# CPU.net
KiCad netlist of a schematic drawn in Altium Designer
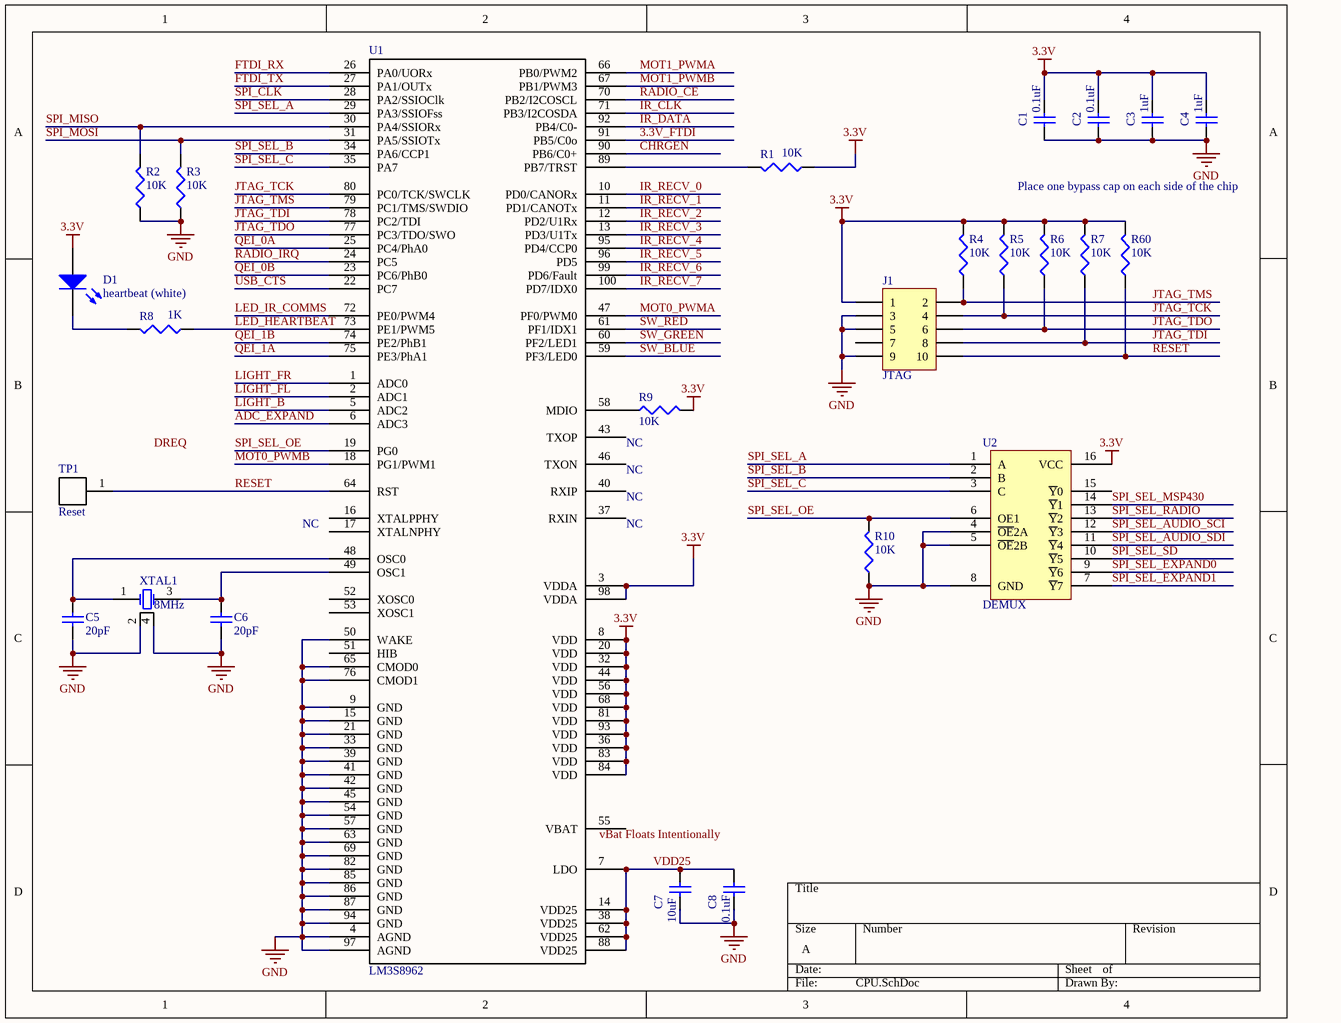
[diagram p0: CPU.SchDoc]

(export (version "E")
  (design (tool "Eeschema 10.0.6"))
  (components
    (comp (ref "C1")
      (value "0.1uF")
      (footprint "CAPC1005L")
      (description "Capacitor (Semiconductor SIM Model)")
      (fields (field (name "Comment") "Cap Semi") (field (name "PUBLISHER") "Altium Limited"))
      (libsource (lib "Miscellaneous Devices") (part "Cap Semi"))
    )
    (comp (ref "C2")
      (value "0.1uF")
      (footprint "CAPC1005L")
      (description "Capacitor (Semiconductor SIM Model)")
      (fields (field (name "Comment") "Cap Semi") (field (name "PUBLISHER") "Altium Limited"))
      (libsource (lib "Miscellaneous Devices") (part "Cap Semi"))
    )
    (comp (ref "C3")
      (value "1uF")
      (footprint "CAPC1608L")
      (description "Capacitor (Semiconductor SIM Model)")
      (fields (field (name "Comment") "Cap Semi") (field (name "PUBLISHER") "Altium Limited"))
      (libsource (lib "Miscellaneous Devices") (part "Cap Semi"))
    )
    (comp (ref "C4")
      (value "1uF")
      (footprint "CAPC1608L")
      (description "Capacitor (Semiconductor SIM Model)")
      (fields (field (name "Comment") "Cap Semi") (field (name "PUBLISHER") "Altium Limited"))
      (libsource (lib "Miscellaneous Devices") (part "Cap Semi"))
    )
    (comp (ref "C5")
      (value "20pF")
      (footprint "CAPC1005L")
      (description "Capacitor (Semiconductor SIM Model)")
      (fields (field (name "Comment") "Cap Semi") (field (name "PUBLISHER") "Altium Limited"))
      (libsource (lib "Miscellaneous Devices") (part "Cap Semi"))
    )
    (comp (ref "C6")
      (value "20pF")
      (footprint "CAPC1005L")
      (description "Capacitor (Semiconductor SIM Model)")
      (fields (field (name "Comment") "Cap Semi") (field (name "PUBLISHER") "Altium Limited"))
      (libsource (lib "Miscellaneous Devices") (part "Cap Semi"))
    )
    (comp (ref "C7")
      (value "10uF")
      (footprint "CAPC1608L")
      (description "Capacitor (Semiconductor SIM Model)")
      (fields (field (name "Comment") "Cap Semi") (field (name "PUBLISHER") "Altium Limited"))
      (libsource (lib "Miscellaneous Devices") (part "Cap Semi"))
    )
    (comp (ref "C8")
      (value "0.1uF")
      (footprint "CAPC1005L")
      (description "Capacitor (Semiconductor SIM Model)")
      (fields (field (name "Comment") "Cap Semi") (field (name "PUBLISHER") "Altium Limited"))
      (libsource (lib "Miscellaneous Devices") (part "Cap Semi"))
    )
    (comp (ref "D1")
      (value "heartbeat (white)")
      (footprint "SurfaceMount(603)")
      (libsource (lib "mrone") (part "LED"))
    )
    (comp (ref "J1")
      (value "JTAG")
      (footprint "JTAG-10")
      (description "Header, 5-Pin, Dual row, Right Angle")
      (fields (field (name "PUBLISHER") "Altium Limited"))
      (libsource (lib "Miscellaneous Connectors") (part "Header 5X2H"))
    )
    (comp (ref "R1")
      (value "10K")
      (footprint "RESC1608L")
      (description "Resistor")
      (fields (field (name "Comment") "Res3") (field (name "PUBLISHER") "Altium Limited"))
      (libsource (lib "Miscellaneous Devices") (part "Res3"))
    )
    (comp (ref "R2")
      (value "10K")
      (footprint "RESC1608L")
      (description "Resistor")
      (fields (field (name "Comment") "Res3") (field (name "PUBLISHER") "Altium Limited"))
      (libsource (lib "Miscellaneous Devices") (part "Res3"))
    )
    (comp (ref "R3")
      (value "10K")
      (footprint "RESC1608L")
      (description "Resistor")
      (fields (field (name "Comment") "Res3") (field (name "PUBLISHER") "Altium Limited"))
      (libsource (lib "Miscellaneous Devices") (part "Res3"))
    )
    (comp (ref "R4")
      (value "10K")
      (footprint "RESC1608L")
      (description "Resistor")
      (fields (field (name "Comment") "Res3") (field (name "PUBLISHER") "Altium Limited"))
      (libsource (lib "Miscellaneous Devices") (part "Res3"))
    )
    (comp (ref "R5")
      (value "10K")
      (footprint "RESC1608L")
      (description "Resistor")
      (fields (field (name "Comment") "Res3") (field (name "PUBLISHER") "Altium Limited"))
      (libsource (lib "Miscellaneous Devices") (part "Res3"))
    )
    (comp (ref "R6")
      (value "10K")
      (footprint "RESC1608L")
      (description "Resistor")
      (fields (field (name "Comment") "Res3") (field (name "PUBLISHER") "Altium Limited"))
      (libsource (lib "Miscellaneous Devices") (part "Res3"))
    )
    (comp (ref "R7")
      (value "10K")
      (footprint "RESC1608L")
      (description "Resistor")
      (fields (field (name "Comment") "Res3") (field (name "PUBLISHER") "Altium Limited"))
      (libsource (lib "Miscellaneous Devices") (part "Res3"))
    )
    (comp (ref "R8")
      (value "1K")
      (footprint "RESC1608L")
      (description "Resistor")
      (fields (field (name "Comment") "Res3") (field (name "PUBLISHER") "Altium Limited"))
      (libsource (lib "Miscellaneous Devices") (part "Res3"))
    )
    (comp (ref "R9")
      (value "10K")
      (footprint "RESC1608L")
      (description "Resistor")
      (fields (field (name "Comment") "Res3") (field (name "PUBLISHER") "Altium Limited"))
      (libsource (lib "Miscellaneous Devices") (part "Res3"))
    )
    (comp (ref "R10")
      (value "10K")
      (footprint "RESC1608L")
      (description "Resistor")
      (fields (field (name "Comment") "Res3") (field (name "PUBLISHER") "Altium Limited"))
      (libsource (lib "Miscellaneous Devices") (part "Res3"))
    )
    (comp (ref "R60")
      (value "10K")
      (footprint "RESC1608L")
      (description "Resistor")
      (fields (field (name "Comment") "Res3") (field (name "PUBLISHER") "Altium Limited"))
      (libsource (lib "Miscellaneous Devices") (part "Res3"))
    )
    (comp (ref "TP1") (value "Reset") (footprint "TestPoint") (libsource (lib "mrone") (part "TestPoint")))
    (comp (ref "U1")
      (value "LM3S8962")
      (footprint "LQFP-100")
      (libsource (lib "Schematic Components") (part "LM3S8962"))
    )
    (comp (ref "U2") (value "DEMUX") (footprint "TSSOP-16") (libsource (lib "mrone") (part "DEMUX")))
    (comp (ref "XTAL1") (value "8MHz") (footprint "CRYSTAL") (libsource (lib "mrone") (part "Crystal")))
  )
  (nets
    (net (code "1") (name "/3.3V_FTDI") (class "Default")
      (node (ref "U1") (pin "91") (pinfunction "PB5/C0o_91") (pintype "passive"))
    )
    (net (code "2") (name "/ADC_EXPAND") (class "Default")
      (node (ref "U1") (pin "6") (pinfunction "ADC3_6") (pintype "passive"))
    )
    (net (code "3") (name "/CHRGEN") (class "Default")
      (node (ref "U1") (pin "90") (pinfunction "PB6/C0+_90") (pintype "passive"))
    )
    (net (code "5") (name "/FTDI_RX") (class "Default")
      (node (ref "U1") (pin "26") (pinfunction "PA0/UORx_26") (pintype "passive"))
    )
    (net (code "6") (name "/FTDI_TX") (class "Default")
      (node (ref "U1") (pin "27") (pinfunction "PA1/OUTx_27") (pintype "passive"))
    )
    (net (code "7") (name "/IR_CLK") (class "Default")
      (node (ref "U1") (pin "71") (pinfunction "PB3/I2COSDA_71") (pintype "passive"))
    )
    (net (code "8") (name "/IR_DATA") (class "Default")
      (node (ref "U1") (pin "92") (pinfunction "PB4/C0-_92") (pintype "passive"))
    )
    (net (code "9") (name "/IR_RECV_0") (class "Default")
      (node (ref "U1") (pin "10") (pinfunction "PD0/CANORx_10") (pintype "passive"))
    )
    (net (code "10") (name "/IR_RECV_1") (class "Default")
      (node (ref "U1") (pin "11") (pinfunction "PD1/CANOTx_11") (pintype "passive"))
    )
    (net (code "11") (name "/IR_RECV_2") (class "Default")
      (node (ref "U1") (pin "12") (pinfunction "PD2/U1Rx_12") (pintype "passive"))
    )
    (net (code "12") (name "/IR_RECV_3") (class "Default")
      (node (ref "U1") (pin "13") (pinfunction "PD3/U1Tx_13") (pintype "passive"))
    )
    (net (code "13") (name "/IR_RECV_4") (class "Default")
      (node (ref "U1") (pin "95") (pinfunction "PD4/CCP0_95") (pintype "passive"))
    )
    (net (code "14") (name "/IR_RECV_5") (class "Default")
      (node (ref "U1") (pin "96") (pinfunction "PD5_96") (pintype "passive"))
    )
    (net (code "15") (name "/IR_RECV_6") (class "Default")
      (node (ref "U1") (pin "99") (pinfunction "PD6/Fault_99") (pintype "passive"))
    )
    (net (code "16") (name "/IR_RECV_7") (class "Default")
      (node (ref "U1") (pin "100") (pinfunction "PD7/IDX0_100") (pintype "passive"))
    )
    (net (code "17") (name "/JTAG_TCK") (class "Default")
      (node (ref "J1") (pin "4") (pinfunction "4_4") (pintype "passive"))
      (node (ref "R5") (pin "1") (pinfunction "1_1") (pintype "passive"))
      (node (ref "U1") (pin "80") (pinfunction "PC0/TCK/SWCLK_80") (pintype "passive"))
    )
    (net (code "18") (name "/JTAG_TDI") (class "Default")
      (node (ref "J1") (pin "8") (pinfunction "8_8") (pintype "passive"))
      (node (ref "R7") (pin "1") (pinfunction "1_1") (pintype "passive"))
      (node (ref "U1") (pin "78") (pinfunction "PC2/TDI_78") (pintype "passive"))
    )
    (net (code "19") (name "/JTAG_TDO") (class "Default")
      (node (ref "J1") (pin "6") (pinfunction "6_6") (pintype "passive"))
      (node (ref "R6") (pin "1") (pinfunction "1_1") (pintype "passive"))
      (node (ref "U1") (pin "77") (pinfunction "PC3/TDO/SWO_77") (pintype "passive"))
    )
    (net (code "20") (name "/JTAG_TMS") (class "Default")
      (node (ref "J1") (pin "2") (pinfunction "2_2") (pintype "passive"))
      (node (ref "R4") (pin "1") (pinfunction "1_1") (pintype "passive"))
      (node (ref "U1") (pin "79") (pinfunction "PC1/TMS/SWDIO_79") (pintype "passive"))
    )
    (net (code "21") (name "/LED_HEARTBEAT") (class "Default")
      (node (ref "R8") (pin "1") (pinfunction "1_1") (pintype "passive"))
      (node (ref "U1") (pin "73") (pinfunction "PE1/PWM5_73") (pintype "passive"))
    )
    (net (code "22") (name "/LED_IR_COMMS") (class "Default")
      (node (ref "U1") (pin "72") (pinfunction "PE0/PWM4_72") (pintype "passive"))
    )
    (net (code "23") (name "/LIGHT_B") (class "Default")
      (node (ref "U1") (pin "5") (pinfunction "ADC2_5") (pintype "passive"))
    )
    (net (code "24") (name "/LIGHT_FL") (class "Default")
      (node (ref "U1") (pin "2") (pinfunction "ADC1_2") (pintype "passive"))
    )
    (net (code "25") (name "/LIGHT_FR") (class "Default")
      (node (ref "U1") (pin "1") (pinfunction "ADC0_1") (pintype "passive"))
    )
    (net (code "26") (name "/MOT0_PWMA") (class "Default")
      (node (ref "U1") (pin "47") (pinfunction "PF0/PWM0_47") (pintype "passive"))
    )
    (net (code "27") (name "/MOT0_PWMB") (class "Default")
      (node (ref "U1") (pin "18") (pinfunction "PG1/PWM1_18") (pintype "passive"))
    )
    (net (code "28") (name "/MOT1_PWMA") (class "Default")
      (node (ref "U1") (pin "66") (pinfunction "PB0/PWM2_66") (pintype "passive"))
    )
    (net (code "29") (name "/MOT1_PWMB") (class "Default")
      (node (ref "U1") (pin "67") (pinfunction "PB1/PWM3_67") (pintype "passive"))
    )
    (net (code "30") (name "/QEI_0A") (class "Default")
      (node (ref "U1") (pin "25") (pinfunction "PC4/PhA0_25") (pintype "passive"))
    )
    (net (code "31") (name "/QEI_0B") (class "Default")
      (node (ref "U1") (pin "23") (pinfunction "PC6/PhB0_23") (pintype "passive"))
    )
    (net (code "32") (name "/QEI_1A") (class "Default")
      (node (ref "U1") (pin "75") (pinfunction "PE3/PhA1_75") (pintype "passive"))
    )
    (net (code "33") (name "/QEI_1B") (class "Default")
      (node (ref "U1") (pin "74") (pinfunction "PE2/PhB1_74") (pintype "passive"))
    )
    (net (code "34") (name "/RADIO_CE") (class "Default")
      (node (ref "U1") (pin "70") (pinfunction "PB2/I2COSCL_70") (pintype "passive"))
    )
    (net (code "35") (name "/RADIO_IRQ") (class "Default")
      (node (ref "U1") (pin "24") (pinfunction "PC5_24") (pintype "passive"))
    )
    (net (code "36") (name "/RESET") (class "Default")
      (node (ref "J1") (pin "10") (pinfunction "10_10") (pintype "passive"))
      (node (ref "R60") (pin "1") (pinfunction "1_1") (pintype "passive"))
      (node (ref "TP1") (pin "1") (pintype "passive"))
      (node (ref "U1") (pin "64") (pinfunction "RST_64") (pintype "passive"))
    )
    (net (code "37") (name "/SPI_CLK") (class "Default")
      (node (ref "U1") (pin "28") (pinfunction "PA2/SSIOClk_28") (pintype "passive"))
    )
    (net (code "38") (name "/SPI_MISO") (class "Default")
      (node (ref "R2") (pin "2") (pinfunction "2_2") (pintype "passive"))
      (node (ref "U1") (pin "30") (pinfunction "PA4/SSIORx_30") (pintype "passive"))
    )
    (net (code "39") (name "/SPI_MOSI") (class "Default")
      (node (ref "R3") (pin "2") (pinfunction "2_2") (pintype "passive"))
      (node (ref "U1") (pin "31") (pinfunction "PA5/SSIOTx_31") (pintype "passive"))
    )
    (net (code "40") (name "/SPI_SEL_A") (class "Default")
      (node (ref "U1") (pin "29") (pinfunction "PA3/SSIOFss_29") (pintype "passive"))
      (node (ref "U2") (pin "1") (pinfunction "A_1") (pintype "passive"))
    )
    (net (code "41") (name "/SPI_SEL_AUDIO_SCI") (class "Default")
      (node (ref "U2") (pin "12") (pinfunction "~{Y}3_12") (pintype "passive"))
    )
    (net (code "42") (name "/SPI_SEL_AUDIO_SDI") (class "Default")
      (node (ref "U2") (pin "11") (pinfunction "~{Y}4_11") (pintype "passive"))
    )
    (net (code "43") (name "/SPI_SEL_B") (class "Default")
      (node (ref "U1") (pin "34") (pinfunction "PA6/CCP1_34") (pintype "passive"))
      (node (ref "U2") (pin "2") (pinfunction "B_2") (pintype "passive"))
    )
    (net (code "44") (name "/SPI_SEL_C") (class "Default")
      (node (ref "U1") (pin "35") (pinfunction "PA7_35") (pintype "passive"))
      (node (ref "U2") (pin "3") (pinfunction "C_3") (pintype "passive"))
    )
    (net (code "45") (name "/SPI_SEL_EXPAND0") (class "Default")
      (node (ref "U2") (pin "9") (pinfunction "~{Y}6_9") (pintype "passive"))
    )
    (net (code "46") (name "/SPI_SEL_EXPAND1") (class "Default")
      (node (ref "U2") (pin "7") (pinfunction "~{Y}7_7") (pintype "passive"))
    )
    (net (code "47") (name "/SPI_SEL_MSP430") (class "Default")
      (node (ref "U2") (pin "14") (pinfunction "~{Y}1_14") (pintype "passive"))
    )
    (net (code "48") (name "/SPI_SEL_OE") (class "Default")
      (node (ref "R10") (pin "2") (pinfunction "2_2") (pintype "passive"))
      (node (ref "U1") (pin "19") (pinfunction "PG0_19") (pintype "passive"))
      (node (ref "U2") (pin "6") (pinfunction "OE1_6") (pintype "passive"))
    )
    (net (code "49") (name "/SPI_SEL_RADIO") (class "Default")
      (node (ref "U2") (pin "13") (pinfunction "~{Y}2_13") (pintype "passive"))
    )
    (net (code "50") (name "/SPI_SEL_SD") (class "Default")
      (node (ref "U2") (pin "10") (pinfunction "~{Y}5_10") (pintype "passive"))
    )
    (net (code "51") (name "/SW_BLUE") (class "Default")
      (node (ref "U1") (pin "59") (pinfunction "PF3/LED0_59") (pintype "passive"))
    )
    (net (code "52") (name "/SW_GREEN") (class "Default")
      (node (ref "U1") (pin "60") (pinfunction "PF2/LED1_60") (pintype "passive"))
    )
    (net (code "53") (name "/SW_RED") (class "Default")
      (node (ref "U1") (pin "61") (pinfunction "PF1/IDX1_61") (pintype "passive"))
    )
    (net (code "54") (name "/USB_CTS") (class "Default")
      (node (ref "U1") (pin "22") (pinfunction "PC7_22") (pintype "passive"))
    )
    (net (code "55") (name "/VDD25") (class "Default")
      (node (ref "C7") (pin "2") (pinfunction "2_2") (pintype "passive"))
      (node (ref "C8") (pin "2") (pinfunction "2_2") (pintype "passive"))
      (node (ref "U1") (pin "14") (pinfunction "VDD25_14") (pintype "passive"))
      (node (ref "U1") (pin "38") (pinfunction "VDD25_38") (pintype "passive"))
      (node (ref "U1") (pin "62") (pinfunction "VDD25_62") (pintype "passive"))
      (node (ref "U1") (pin "7") (pinfunction "LDO_7") (pintype "passive"))
      (node (ref "U1") (pin "88") (pinfunction "VDD25_88") (pintype "passive"))
    )
    (net (code "56") (name "3.3V") (class "Default")
      (node (ref "C1") (pin "2") (pinfunction "2_2") (pintype "passive"))
      (node (ref "C2") (pin "2") (pinfunction "2_2") (pintype "passive"))
      (node (ref "C3") (pin "2") (pinfunction "2_2") (pintype "passive"))
      (node (ref "C4") (pin "2") (pinfunction "2_2") (pintype "passive"))
      (node (ref "D1") (pin "1") (pinfunction "A_1") (pintype "passive"))
      (node (ref "J1") (pin "1") (pinfunction "1_1") (pintype "passive"))
      (node (ref "R1") (pin "1") (pinfunction "1_1") (pintype "passive"))
      (node (ref "R4") (pin "2") (pinfunction "2_2") (pintype "passive"))
      (node (ref "R5") (pin "2") (pinfunction "2_2") (pintype "passive"))
      (node (ref "R6") (pin "2") (pinfunction "2_2") (pintype "passive"))
      (node (ref "R60") (pin "2") (pinfunction "2_2") (pintype "passive"))
      (node (ref "R7") (pin "2") (pinfunction "2_2") (pintype "passive"))
      (node (ref "R9") (pin "2") (pinfunction "2_2") (pintype "passive"))
      (node (ref "U1") (pin "20") (pinfunction "VDD_20") (pintype "passive"))
      (node (ref "U1") (pin "3") (pinfunction "VDDA_3") (pintype "passive"))
      (node (ref "U1") (pin "32") (pinfunction "VDD_32") (pintype "passive"))
      (node (ref "U1") (pin "36") (pinfunction "VDD_36") (pintype "passive"))
      (node (ref "U1") (pin "44") (pinfunction "VDD_44") (pintype "passive"))
      (node (ref "U1") (pin "56") (pinfunction "VDD_56") (pintype "passive"))
      (node (ref "U1") (pin "68") (pinfunction "VDD_68") (pintype "passive"))
      (node (ref "U1") (pin "8") (pinfunction "VDD_8") (pintype "passive"))
      (node (ref "U1") (pin "81") (pinfunction "VDD_81") (pintype "passive"))
      (node (ref "U1") (pin "83") (pinfunction "VDD_83") (pintype "passive"))
      (node (ref "U1") (pin "84") (pinfunction "VDD_84") (pintype "passive"))
      (node (ref "U1") (pin "93") (pinfunction "VDD_93") (pintype "passive"))
      (node (ref "U1") (pin "98") (pinfunction "VDDA_98") (pintype "passive"))
      (node (ref "U2") (pin "16") (pinfunction "VCC_16") (pintype "passive"))
    )
    (net (code "57") (name "GND") (class "Default")
      (node (ref "C1") (pin "1") (pinfunction "1_1") (pintype "passive"))
      (node (ref "C2") (pin "1") (pinfunction "1_1") (pintype "passive"))
      (node (ref "C3") (pin "1") (pinfunction "1_1") (pintype "passive"))
      (node (ref "C4") (pin "1") (pinfunction "1_1") (pintype "passive"))
      (node (ref "C5") (pin "1") (pinfunction "1_1") (pintype "passive"))
      (node (ref "C6") (pin "1") (pinfunction "1_1") (pintype "passive"))
      (node (ref "C7") (pin "1") (pinfunction "1_1") (pintype "passive"))
      (node (ref "C8") (pin "1") (pinfunction "1_1") (pintype "passive"))
      (node (ref "J1") (pin "3") (pinfunction "3_3") (pintype "passive"))
      (node (ref "J1") (pin "5") (pinfunction "5_5") (pintype "passive"))
      (node (ref "J1") (pin "9") (pinfunction "9_9") (pintype "passive"))
      (node (ref "R10") (pin "1") (pinfunction "1_1") (pintype "passive"))
      (node (ref "R2") (pin "1") (pinfunction "1_1") (pintype "passive"))
      (node (ref "R3") (pin "1") (pinfunction "1_1") (pintype "passive"))
      (node (ref "U1") (pin "15") (pinfunction "GND_15") (pintype "passive"))
      (node (ref "U1") (pin "21") (pinfunction "GND_21") (pintype "passive"))
      (node (ref "U1") (pin "33") (pinfunction "GND_33") (pintype "passive"))
      (node (ref "U1") (pin "39") (pinfunction "GND_39") (pintype "passive"))
      (node (ref "U1") (pin "4") (pinfunction "AGND_4") (pintype "passive"))
      (node (ref "U1") (pin "41") (pinfunction "GND_41") (pintype "passive"))
      (node (ref "U1") (pin "42") (pinfunction "GND_42") (pintype "passive"))
      (node (ref "U1") (pin "45") (pinfunction "GND_45") (pintype "passive"))
      (node (ref "U1") (pin "50") (pinfunction "WAKE_50") (pintype "passive"))
      (node (ref "U1") (pin "54") (pinfunction "GND_54") (pintype "passive"))
      (node (ref "U1") (pin "57") (pinfunction "GND_57") (pintype "passive"))
      (node (ref "U1") (pin "63") (pinfunction "GND_63") (pintype "passive"))
      (node (ref "U1") (pin "65") (pinfunction "CMOD0_65") (pintype "passive"))
      (node (ref "U1") (pin "69") (pinfunction "GND_69") (pintype "passive"))
      (node (ref "U1") (pin "76") (pinfunction "CMOD1_76") (pintype "passive"))
      (node (ref "U1") (pin "82") (pinfunction "GND_82") (pintype "passive"))
      (node (ref "U1") (pin "85") (pinfunction "GND_85") (pintype "passive"))
      (node (ref "U1") (pin "86") (pinfunction "GND_86") (pintype "passive"))
      (node (ref "U1") (pin "87") (pinfunction "GND_87") (pintype "passive"))
      (node (ref "U1") (pin "9") (pinfunction "GND_9") (pintype "passive"))
      (node (ref "U1") (pin "94") (pinfunction "GND_94") (pintype "passive"))
      (node (ref "U1") (pin "97") (pinfunction "AGND_97") (pintype "passive"))
      (node (ref "U2") (pin "4") (pinfunction "~{OE}2A_4") (pintype "passive"))
      (node (ref "U2") (pin "5") (pinfunction "~{OE}2B_5") (pintype "passive"))
      (node (ref "U2") (pin "8") (pinfunction "GND_8") (pintype "passive"))
      (node (ref "XTAL1") (pin "2") (pinfunction "GND_2") (pintype "passive"))
      (node (ref "XTAL1") (pin "4") (pinfunction "GND_4") (pintype "passive"))
    )
    (net (code "58") (name "Net-(D1-K)") (class "Default")
      (node (ref "D1") (pin "2") (pinfunction "K_2") (pintype "passive"))
      (node (ref "R8") (pin "2") (pinfunction "2_2") (pintype "passive"))
    )
    (net (code "59") (name "Net-(U1-MDIO)") (class "Default")
      (node (ref "R9") (pin "1") (pinfunction "1_1") (pintype "passive"))
      (node (ref "U1") (pin "58") (pinfunction "MDIO_58") (pintype "passive"))
    )
    (net (code "60") (name "Net-(U1-OSC0)") (class "Default")
      (node (ref "C5") (pin "2") (pinfunction "2_2") (pintype "passive"))
      (node (ref "U1") (pin "48") (pinfunction "OSC0_48") (pintype "passive"))
      (node (ref "XTAL1") (pin "1") (pinfunction "OSC1_1") (pintype "passive"))
    )
    (net (code "61") (name "Net-(U1-OSC1)") (class "Default")
      (node (ref "C6") (pin "2") (pinfunction "2_2") (pintype "passive"))
      (node (ref "U1") (pin "49") (pinfunction "OSC1_49") (pintype "passive"))
      (node (ref "XTAL1") (pin "3") (pinfunction "OSC2_3") (pintype "passive"))
    )
    (net (code "62") (name "Net-(U1-PB7{slash}TRST)") (class "Default")
      (node (ref "R1") (pin "2") (pinfunction "2_2") (pintype "passive"))
      (node (ref "U1") (pin "89") (pinfunction "PB7/TRST_89") (pintype "passive"))
    )
    (net (code "63") (name "unconnected-(J1-Pad7)") (class "Default")
      (node (ref "J1") (pin "7") (pinfunction "7_7") (pintype "passive"))
    )
    (net (code "64") (name "unconnected-(U1-HIB-Pad51)") (class "Default")
      (node (ref "U1") (pin "51") (pinfunction "HIB_51") (pintype "passive"))
    )
    (net (code "65") (name "unconnected-(U1-RXIN-Pad37)") (class "Default")
      (node (ref "U1") (pin "37") (pinfunction "RXIN_37") (pintype "passive"))
    )
    (net (code "66") (name "unconnected-(U1-RXIP-Pad40)") (class "Default")
      (node (ref "U1") (pin "40") (pinfunction "RXIP_40") (pintype "passive"))
    )
    (net (code "67") (name "unconnected-(U1-TXON-Pad46)") (class "Default")
      (node (ref "U1") (pin "46") (pinfunction "TXON_46") (pintype "passive"))
    )
    (net (code "68") (name "unconnected-(U1-TXOP-Pad43)") (class "Default")
      (node (ref "U1") (pin "43") (pinfunction "TXOP_43") (pintype "passive"))
    )
    (net (code "69") (name "unconnected-(U1-VBAT-Pad55)") (class "Default")
      (node (ref "U1") (pin "55") (pinfunction "VBAT_55") (pintype "passive"))
    )
    (net (code "70") (name "unconnected-(U1-XOSC0-Pad52)") (class "Default")
      (node (ref "U1") (pin "52") (pinfunction "XOSC0_52") (pintype "passive"))
    )
    (net (code "71") (name "unconnected-(U1-XOSC1-Pad53)") (class "Default")
      (node (ref "U1") (pin "53") (pinfunction "XOSC1_53") (pintype "passive"))
    )
    (net (code "72") (name "unconnected-(U1-XTALNPHY-Pad17)") (class "Default")
      (node (ref "U1") (pin "17") (pinfunction "XTALNPHY_17") (pintype "passive"))
    )
    (net (code "73") (name "unconnected-(U1-XTALPPHY-Pad16)") (class "Default")
      (node (ref "U1") (pin "16") (pinfunction "XTALPPHY_16") (pintype "passive"))
    )
    (net (code "74") (name "unconnected-(U2-~{Y}0-Pad15)") (class "Default")
      (node (ref "U2") (pin "15") (pinfunction "~{Y}0_15") (pintype "passive"))
    )
  )
)
